# 3_4G.net
KiCad netlist of a schematic drawn in Altium Designer
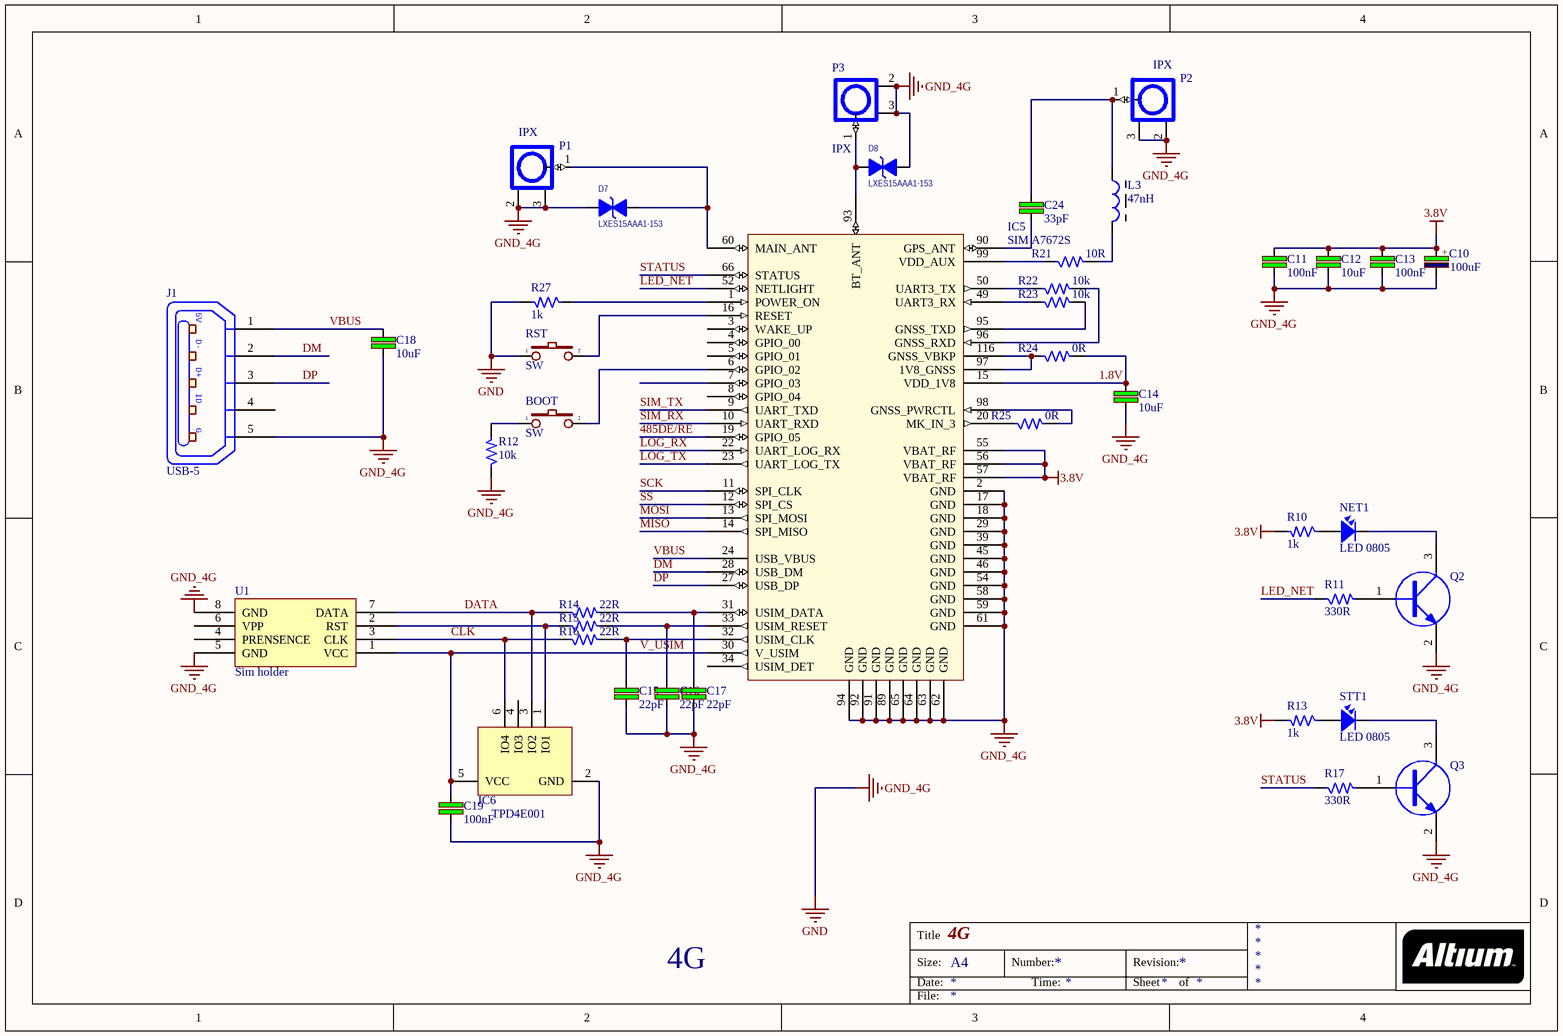
[diagram p0: 3. 4G.SchDoc]

(export (version "E")
  (design (tool "Eeschema 10.0.6"))
  (components
    (comp (ref "BOOT")
      (value "SW")
      (footprint "Anh_Trung:SW1-SMD")
      (description "Switch button 2 pin")
      (libsource (lib "Anh_Trung") (part "SW2"))
    )
    (comp (ref "C10")
      (value "100uF")
      (footprint "EEFSDE")
      (description "Cap SMD")
      (fields
        (field (name "MANUFACTURER") "Samsung Electro-Mechanics")
        (field (name "PART NUMBER") "TCME227M016R0040E")
      )
      (libsource (lib "Anh_Trung") (part "CP4"))
    )
    (comp (ref "C11")
      (value "100nF")
      (footprint "C-0805")
      (description "Cap SMD")
      (fields
        (field (name "MANUFACTURER") "Samsung Electro-Mechanics")
        (field (name "PART NUMBER") "CL21B104KBCNNWC")
      )
      (libsource (lib "") (part "C_1"))
    )
    (comp (ref "C12")
      (value "10uF")
      (footprint "C-0805")
      (description "Cap SMD")
      (fields
        (field (name "MANUFACTURER") "Samsung Electro-Mechanics")
        (field (name "PART NUMBER") "CL21A106KPFNNNG")
      )
      (libsource (lib "") (part "C_1"))
    )
    (comp (ref "C13")
      (value "100nF")
      (footprint "C-0805")
      (description "Cap SMD")
      (fields
        (field (name "MANUFACTURER") "Samsung Electro-Mechanics")
        (field (name "PART NUMBER") "CL21B104KBCNNWC")
      )
      (libsource (lib "") (part "C_1"))
    )
    (comp (ref "C14")
      (value "10uF")
      (footprint "C-0805")
      (description "Cap SMD")
      (fields
        (field (name "MANUFACTURER") "Samsung Electro-Mechanics")
        (field (name "PART NUMBER") "CL21A106KPFNNNG")
      )
      (libsource (lib "") (part "C_1"))
    )
    (comp (ref "C15")
      (value "22pF")
      (footprint "C-0805")
      (description "Cap SMD")
      (fields
        (field (name "MANUFACTURER") "Samsung Electro-Mechanics")
        (field (name "PART NUMBER") "CL21C220JBANFNC")
      )
      (libsource (lib "") (part "C_1"))
    )
    (comp (ref "C16")
      (value "22pF")
      (footprint "C-0805")
      (description "Cap SMD")
      (fields
        (field (name "MANUFACTURER") "Samsung Electro-Mechanics")
        (field (name "PART NUMBER") "CL21C220JBANFNC")
      )
      (libsource (lib "") (part "C_1"))
    )
    (comp (ref "C17")
      (value "22pF")
      (footprint "C-0805")
      (description "Cap SMD")
      (fields
        (field (name "MANUFACTURER") "Samsung Electro-Mechanics")
        (field (name "PART NUMBER") "CL21C220JBANFNC")
      )
      (libsource (lib "") (part "C_1"))
    )
    (comp (ref "C18")
      (value "10uF")
      (footprint "C-0805")
      (description "Cap SMD")
      (fields
        (field (name "MANUFACTURER") "Samsung Electro-Mechanics")
        (field (name "PART NUMBER") "CL21A106KPFNNNG")
      )
      (libsource (lib "") (part "C_2"))
    )
    (comp (ref "C19")
      (value "100nF")
      (footprint "C-0805")
      (description "Cap SMD")
      (fields
        (field (name "MANUFACTURER") "Samsung Electro-Mechanics")
        (field (name "PART NUMBER") "CL21B104KBCNNWC")
      )
      (libsource (lib "") (part "C_1"))
    )
    (comp (ref "C24")
      (value "33pF")
      (footprint "C-0805")
      (description "Cap SMD")
      (fields
        (field (name "MANUFACTURER") "Samsung Electro-Mechanics")
        (field (name "PART NUMBER") "CC0805FRNPO9BN330")
      )
      (libsource (lib "Anh_Trung") (part "C"))
    )
    (comp (ref "D7")
      (value "LXES15AAA1-153")
      (footprint "Anh_Trung:R-0402")
      (description "TVS DIODE 4VWM 1005")
      (fields (field (name "MANUFACTURER") "Murata Electronics"))
      (libsource (lib "Anh_Trung") (part "TVS"))
    )
    (comp (ref "D8")
      (value "LXES15AAA1-153")
      (footprint "Anh_Trung:R-0402")
      (description "TVS DIODE 4VWM 1005")
      (fields (field (name "MANUFACTURER") "Murata Electronics"))
      (libsource (lib "Anh_Trung") (part "TVS"))
    )
    (comp (ref "IC5")
      (value "SIM A7672S")
      (footprint "SIM A7672S")
      (description "SIM A7672S-CAT-M1")
      (libsource (lib "Anh_Trung") (part "SIM A7672S"))
    )
    (comp (ref "IC6")
      (value "TPD4E001")
      (footprint "SOT23-6 - 2")
      (fields (field (name "MANUFACTURER") "Texas Instruments") (field (name "PART NUMBER") "TPD4E001RDBVR"))
      (libsource (lib "Anh_Trung") (part "TPD4E001"))
    )
    (comp (ref "J1")
      (value "USB-5")
      (footprint "USB-M1")
      (fields (field (name "MANUFACTURER") "FCI"))
      (libsource (lib "Anh_Trung") (part "USB-5"))
    )
    (comp (ref "L3")
      (value "47nH")
      (footprint "L-0603")
      (description "FIXED IND 47NH 300MA 700MOHM SMD")
      (fields (field (name "MANUFACTURER") "Taiyo Yuden") (field (name "PART NUMBER") "HK160847NJ-T"))
      (libsource (lib "Anh_Trung") (part "Inductor Ferit"))
    )
    (comp (ref "NET1")
      (value "LED 0805")
      (footprint "LED-0805")
      (description "LED RED DIFFUSED 0805 SMD")
      (fields
        (field (name "MANUFACTURER") "OSRAM Opto Semiconductors Inc.")
        (field (name "PART NUMBER") "LS R976-NR-1")
      )
      (libsource (lib "Anh_Trung") (part "LED"))
    )
    (comp (ref "P1")
      (value "IPX")
      (footprint "IPXS")
      (description "Antenna GSM GPS")
      (fields
        (field (name "MANUFACTURER") "TE Connectivity AMP Connectors")
        (field (name "PART NUMBER") "2334884-1")
      )
      (libsource (lib "") (part "IPXSx66_1"))
    )
    (comp (ref "P2")
      (value "IPX")
      (footprint "IPXS")
      (description "Antenna GSM GPS")
      (fields
        (field (name "MANUFACTURER") "TE Connectivity AMP Connectors")
        (field (name "PART NUMBER") "2334884-1")
      )
      (libsource (lib "Anh_Trung") (part "IPXSx66"))
    )
    (comp (ref "P3")
      (value "IPX")
      (footprint "IPXS")
      (description "Antenna GSM GPS")
      (fields
        (field (name "MANUFACTURER") "TE Connectivity AMP Connectors")
        (field (name "PART NUMBER") "2334884-1")
      )
      (libsource (lib "Anh_Trung") (part "IPXSx66"))
    )
    (comp (ref "Q2")
      (value "C1815(MMBT4401)")
      (footprint "SOT23-3")
      (description "Transistor C1815, SOT23")
      (fields (field (name "MANUFACTURER") "Fairchild Semiconductor") (field (name "PART NUMBER") "MMBT4401"))
      (libsource (lib "Anh_Trung") (part "NPN"))
    )
    (comp (ref "Q3")
      (value "C1815(MMBT4401)")
      (footprint "SOT23-3")
      (description "Transistor C1815, SOT23")
      (fields (field (name "MANUFACTURER") "Fairchild Semiconductor") (field (name "PART NUMBER") "MMBT4401"))
      (libsource (lib "Anh_Trung") (part "NPN"))
    )
    (comp (ref "R10")
      (value "1k")
      (footprint "R-0805")
      (description "Resistor 1/4W")
      (fields (field (name "MANUFACTURER") "Yageo") (field (name "PART NUMBER") "RC0805FR-071KL"))
      (libsource (lib "Anh_Trung") (part "R"))
    )
    (comp (ref "R11")
      (value "330R")
      (footprint "R-0805")
      (description "Resistor 1/4W")
      (fields (field (name "MANUFACTURER") "Yageo") (field (name "PART NUMBER") "RC0805FR-07330RL"))
      (libsource (lib "Anh_Trung") (part "R"))
    )
    (comp (ref "R12")
      (value "10k")
      (footprint "R-0805")
      (description "Resistor 1/4W")
      (fields (field (name "MANUFACTURER") "Yageo") (field (name "PART NUMBER") "RC0805FR-0710KL"))
      (libsource (lib "Anh_Trung") (part "R"))
    )
    (comp (ref "R13")
      (value "1k")
      (footprint "R-0805")
      (description "Resistor 1/4W")
      (fields (field (name "MANUFACTURER") "Yageo") (field (name "PART NUMBER") "RC0805FR-071KL"))
      (libsource (lib "Anh_Trung") (part "R"))
    )
    (comp (ref "R14")
      (value "22R")
      (footprint "R-0805")
      (description "Resistor 1/4W")
      (fields (field (name "MANUFACTURER") "Yageo") (field (name "PART NUMBER") "RC0805FR-0722RL"))
      (libsource (lib "Anh_Trung") (part "R"))
    )
    (comp (ref "R15")
      (value "22R")
      (footprint "R-0805")
      (description "Resistor 1/4W")
      (fields (field (name "MANUFACTURER") "Yageo") (field (name "PART NUMBER") "RC0805FR-0722RL"))
      (libsource (lib "Anh_Trung") (part "R"))
    )
    (comp (ref "R16")
      (value "22R")
      (footprint "R-0805")
      (description "Resistor 1/4W")
      (fields (field (name "MANUFACTURER") "Yageo") (field (name "PART NUMBER") "RC0805FR-0722RL"))
      (libsource (lib "Anh_Trung") (part "R"))
    )
    (comp (ref "R17")
      (value "330R")
      (footprint "R-0805")
      (description "Resistor 1/4W")
      (fields (field (name "MANUFACTURER") "Yageo") (field (name "PART NUMBER") "RC0805FR-07330RL"))
      (libsource (lib "Anh_Trung") (part "R"))
    )
    (comp (ref "R21")
      (value "10R")
      (footprint "R-0805")
      (description "Resistor 1/4W")
      (fields (field (name "MANUFACTURER") "Yageo") (field (name "PART NUMBER") "RC0805FR-0710RL"))
      (libsource (lib "Anh_Trung") (part "R"))
    )
    (comp (ref "R22")
      (value "10k")
      (footprint "R-0805")
      (description "Resistor 1/4W")
      (fields (field (name "MANUFACTURER") "Yageo") (field (name "PART NUMBER") "RC0805FR-0710RL"))
      (libsource (lib "Anh_Trung") (part "R"))
    )
    (comp (ref "R23")
      (value "10k")
      (footprint "R-0805")
      (description "Resistor 1/4W")
      (fields (field (name "MANUFACTURER") "Yageo") (field (name "PART NUMBER") "RC0805FR-0710RL"))
      (libsource (lib "Anh_Trung") (part "R"))
    )
    (comp (ref "R24")
      (value "0R")
      (footprint "R-0805")
      (description "Resistor 1/4W")
      (fields (field (name "MANUFACTURER") "Yageo") (field (name "PART NUMBER") "RC0805FR-0710RL"))
      (libsource (lib "Anh_Trung") (part "R"))
    )
    (comp (ref "R25")
      (value "0R")
      (footprint "R-0805")
      (description "Resistor 1/4W")
      (fields (field (name "MANUFACTURER") "Yageo") (field (name "PART NUMBER") "RC0805FR-0710RL"))
      (libsource (lib "Anh_Trung") (part "R"))
    )
    (comp (ref "R27")
      (value "1k")
      (footprint "R-0805")
      (description "Resistor 1/4W")
      (fields (field (name "MANUFACTURER") "Yageo") (field (name "PART NUMBER") "RC0805FR-071KL"))
      (libsource (lib "Anh_Trung") (part "R"))
    )
    (comp (ref "RST")
      (value "SW")
      (footprint "Anh_Trung:SW1-SMD")
      (description "Switch button 2 pin")
      (libsource (lib "Anh_Trung") (part "SW2"))
    )
    (comp (ref "STT1")
      (value "LED 0805")
      (footprint "LED-0805")
      (description "LED RED DIFFUSED 0805 SMD")
      (fields
        (field (name "MANUFACTURER") "OSRAM Opto Semiconductors Inc.")
        (field (name "PART NUMBER") "LS R976-NR-1")
      )
      (libsource (lib "Anh_Trung") (part "LED"))
    )
    (comp (ref "U1")
      (value "Sim holder")
      (footprint "SIM_MicroSIM 6P Flip")
      (libsource (lib "Anh_Trung") (part "Component_1"))
    )
  )
  (nets
    (net (code "1") (name "/1.8V") (class "Default")
      (node (ref "C14") (pin "1") (pinfunction "1_1") (pintype "passive"))
      (node (ref "IC5") (pin "15") (pinfunction "VDD_1V8_15") (pintype "passive"))
      (node (ref "R24") (pin "2") (pinfunction "2_2") (pintype "passive"))
    )
    (net (code "2") (name "/485DE{slash}RE") (class "Default")
      (node (ref "IC5") (pin "19") (pinfunction "GPIO_05_19") (pintype "bidirectional"))
    )
    (net (code "3") (name "/CLK") (class "Default")
      (node (ref "IC6") (pin "6") (pinfunction "IO4_6") (pintype "passive"))
      (node (ref "R16") (pin "1") (pinfunction "1_1") (pintype "passive"))
      (node (ref "U1") (pin "3") (pinfunction "CLK_3") (pintype "passive"))
    )
    (net (code "4") (name "/DATA") (class "Default")
      (node (ref "IC6") (pin "3") (pinfunction "IO2_3") (pintype "passive"))
      (node (ref "R14") (pin "1") (pinfunction "1_1") (pintype "passive"))
      (node (ref "U1") (pin "7") (pinfunction "DATA_7") (pintype "passive"))
    )
    (net (code "5") (name "/DM") (class "Default")
      (node (ref "IC5") (pin "28") (pinfunction "USB_DM_28") (pintype "bidirectional"))
      (node (ref "J1") (pin "2") (pinfunction "P2_2") (pintype "passive"))
    )
    (net (code "6") (name "/DP") (class "Default")
      (node (ref "IC5") (pin "27") (pinfunction "USB_DP_27") (pintype "bidirectional"))
      (node (ref "J1") (pin "3") (pinfunction "P3_3") (pintype "passive"))
    )
    (net (code "7") (name "/LED_NET") (class "Default")
      (node (ref "IC5") (pin "52") (pinfunction "NETLIGHT_52") (pintype "bidirectional"))
      (node (ref "R11") (pin "1") (pinfunction "1_1") (pintype "passive"))
    )
    (net (code "8") (name "/LOG_RX") (class "Default")
      (node (ref "IC5") (pin "22") (pinfunction "UART_LOG_RX_22") (pintype "input"))
    )
    (net (code "9") (name "/LOG_TX") (class "Default")
      (node (ref "IC5") (pin "23") (pinfunction "UART_LOG_TX_23") (pintype "output"))
    )
    (net (code "10") (name "/MISO") (class "Default")
      (node (ref "IC5") (pin "14") (pinfunction "SPI_MISO_14") (pintype "output"))
    )
    (net (code "11") (name "/MOSI") (class "Default")
      (node (ref "IC5") (pin "13") (pinfunction "SPI_MOSI_13") (pintype "output"))
    )
    (net (code "12") (name "/SCK") (class "Default")
      (node (ref "IC5") (pin "11") (pinfunction "SPI_CLK_11") (pintype "bidirectional"))
    )
    (net (code "13") (name "/SIM_RX") (class "Default")
      (node (ref "IC5") (pin "10") (pinfunction "UART_RXD_10") (pintype "input"))
    )
    (net (code "14") (name "/SIM_TX") (class "Default")
      (node (ref "IC5") (pin "9") (pinfunction "UART_TXD_9") (pintype "output"))
    )
    (net (code "15") (name "/SS") (class "Default")
      (node (ref "IC5") (pin "12") (pinfunction "SPI_CS_12") (pintype "bidirectional"))
    )
    (net (code "16") (name "/STATUS") (class "Default")
      (node (ref "IC5") (pin "66") (pinfunction "STATUS_66") (pintype "bidirectional"))
      (node (ref "R17") (pin "1") (pinfunction "1_1") (pintype "passive"))
    )
    (net (code "17") (name "/VBUS") (class "Default")
      (node (ref "C18") (pin "1") (pinfunction "1_1") (pintype "passive"))
      (node (ref "IC5") (pin "24") (pinfunction "USB_VBUS_24") (pintype "passive"))
      (node (ref "J1") (pin "1") (pinfunction "P1_1") (pintype "passive"))
    )
    (net (code "18") (name "/V_USIM") (class "Default")
      (node (ref "C19") (pin "1") (pinfunction "1_1") (pintype "passive"))
      (node (ref "IC5") (pin "30") (pinfunction "V_USIM_30") (pintype "output"))
      (node (ref "IC6") (pin "5") (pinfunction "VCC_5") (pintype "passive"))
      (node (ref "U1") (pin "1") (pinfunction "VCC_1") (pintype "passive"))
    )
    (net (code "19") (name "3.8V") (class "Default")
      (node (ref "C10") (pin "1") (pinfunction "1_1") (pintype "passive"))
      (node (ref "C11") (pin "1") (pinfunction "1_1") (pintype "passive"))
      (node (ref "C12") (pin "1") (pinfunction "1_1") (pintype "passive"))
      (node (ref "C13") (pin "1") (pinfunction "1_1") (pintype "passive"))
      (node (ref "IC5") (pin "55") (pinfunction "VBAT_RF_55") (pintype "passive"))
      (node (ref "IC5") (pin "56") (pinfunction "VBAT_RF_56") (pintype "passive"))
      (node (ref "IC5") (pin "57") (pinfunction "VBAT_RF_57") (pintype "passive"))
      (node (ref "R10") (pin "2") (pinfunction "2_2") (pintype "passive"))
      (node (ref "R13") (pin "2") (pinfunction "2_2") (pintype "passive"))
    )
    (net (code "20") (name "GND") (class "Default")
      (node (ref "C10") (pin "2") (pinfunction "2_2") (pintype "passive"))
      (node (ref "C11") (pin "2") (pinfunction "2_2") (pintype "passive"))
      (node (ref "C12") (pin "2") (pinfunction "2_2") (pintype "passive"))
      (node (ref "C13") (pin "2") (pinfunction "2_2") (pintype "passive"))
      (node (ref "C14") (pin "2") (pinfunction "2_2") (pintype "passive"))
      (node (ref "C15") (pin "2") (pinfunction "2_2") (pintype "passive"))
      (node (ref "C16") (pin "2") (pinfunction "2_2") (pintype "passive"))
      (node (ref "C17") (pin "2") (pinfunction "2_2") (pintype "passive"))
      (node (ref "C18") (pin "2") (pinfunction "2_2") (pintype "passive"))
      (node (ref "C19") (pin "2") (pinfunction "2_2") (pintype "passive"))
      (node (ref "D7") (pin "2") (pinfunction "K_2") (pintype "passive"))
      (node (ref "D8") (pin "1") (pinfunction "A_1") (pintype "passive"))
      (node (ref "IC5") (pin "17") (pinfunction "GND_17") (pintype "passive"))
      (node (ref "IC5") (pin "18") (pinfunction "GND_18") (pintype "passive"))
      (node (ref "IC5") (pin "2") (pinfunction "GND_2") (pintype "passive"))
      (node (ref "IC5") (pin "29") (pinfunction "GND_29") (pintype "passive"))
      (node (ref "IC5") (pin "39") (pinfunction "GND_39") (pintype "passive"))
      (node (ref "IC5") (pin "45") (pinfunction "GND_45") (pintype "passive"))
      (node (ref "IC5") (pin "46") (pinfunction "GND_46") (pintype "passive"))
      (node (ref "IC5") (pin "54") (pinfunction "GND_54") (pintype "passive"))
      (node (ref "IC5") (pin "58") (pinfunction "GND_58") (pintype "passive"))
      (node (ref "IC5") (pin "59") (pinfunction "GND_59") (pintype "passive"))
      (node (ref "IC5") (pin "61") (pinfunction "GND_61") (pintype "passive"))
      (node (ref "IC5") (pin "62") (pinfunction "GND_62") (pintype "passive"))
      (node (ref "IC5") (pin "63") (pinfunction "GND_63") (pintype "passive"))
      (node (ref "IC5") (pin "64") (pinfunction "GND_64") (pintype "passive"))
      (node (ref "IC5") (pin "65") (pinfunction "GND_65") (pintype "passive"))
      (node (ref "IC5") (pin "89") (pinfunction "GND_89") (pintype "passive"))
      (node (ref "IC5") (pin "91") (pinfunction "GND_91") (pintype "passive"))
      (node (ref "IC5") (pin "92") (pinfunction "GND_92") (pintype "passive"))
      (node (ref "IC5") (pin "94") (pinfunction "GND_94") (pintype "passive"))
      (node (ref "IC6") (pin "2") (pinfunction "GND_2") (pintype "passive"))
      (node (ref "J1") (pin "5") (pinfunction "P5_5") (pintype "passive"))
      (node (ref "P1") (pin "2") (pintype "passive"))
      (node (ref "P1") (pin "3") (pintype "passive"))
      (node (ref "P2") (pin "2") (pintype "passive"))
      (node (ref "P2") (pin "3") (pintype "passive"))
      (node (ref "P3") (pin "2") (pintype "passive"))
      (node (ref "P3") (pin "3") (pintype "passive"))
      (node (ref "Q2") (pin "2") (pinfunction "E_2") (pintype "passive"))
      (node (ref "Q3") (pin "2") (pinfunction "E_2") (pintype "passive"))
      (node (ref "R12") (pin "1") (pinfunction "1_1") (pintype "passive"))
      (node (ref "R27") (pin "2") (pinfunction "2_2") (pintype "passive"))
      (node (ref "RST") (pin "1") (pinfunction "1_1") (pintype "passive"))
      (node (ref "U1") (pin "5") (pinfunction "GND_5") (pintype "passive"))
      (node (ref "U1") (pin "8") (pinfunction "GND_8") (pintype "passive"))
    )
    (net (code "21") (name "Net-(BOOT-Pad1)") (class "Default")
      (node (ref "BOOT") (pin "1") (pinfunction "1_1") (pintype "passive"))
      (node (ref "R12") (pin "2") (pinfunction "2_2") (pintype "passive"))
    )
    (net (code "22") (name "Net-(C24-Pad2)") (class "Default")
      (node (ref "C24") (pin "2") (pinfunction "2_2") (pintype "passive"))
      (node (ref "L3") (pin "1") (pinfunction "1_1") (pintype "passive"))
      (node (ref "P2") (pin "1") (pintype "bidirectional"))
    )
    (net (code "23") (name "Net-(D7-A)") (class "Default")
      (node (ref "D7") (pin "1") (pinfunction "A_1") (pintype "passive"))
      (node (ref "IC5") (pin "60") (pinfunction "MAIN_ANT_60") (pintype "bidirectional"))
      (node (ref "P1") (pin "1") (pintype "bidirectional"))
    )
    (net (code "24") (name "Net-(D8-K)") (class "Default")
      (node (ref "D8") (pin "2") (pinfunction "K_2") (pintype "passive"))
      (node (ref "IC5") (pin "93") (pinfunction "BT_ANT_93") (pintype "bidirectional"))
      (node (ref "P3") (pin "1") (pintype "bidirectional"))
    )
    (net (code "25") (name "Net-(IC5-1V8_GNSS)") (class "Default")
      (node (ref "IC5") (pin "116") (pinfunction "GNSS_VBKP_116") (pintype "passive"))
      (node (ref "IC5") (pin "97") (pinfunction "1V8_GNSS_97") (pintype "passive"))
      (node (ref "R24") (pin "1") (pinfunction "1_1") (pintype "passive"))
    )
    (net (code "26") (name "Net-(IC5-GNSS_PWRCTL)") (class "Default")
      (node (ref "IC5") (pin "98") (pinfunction "GNSS_PWRCTL_98") (pintype "input"))
      (node (ref "R25") (pin "2") (pinfunction "2_2") (pintype "passive"))
    )
    (net (code "27") (name "Net-(IC5-GNSS_RXD)") (class "Default")
      (node (ref "IC5") (pin "96") (pinfunction "GNSS_RXD_96") (pintype "input"))
      (node (ref "R22") (pin "2") (pinfunction "2_2") (pintype "passive"))
    )
    (net (code "28") (name "Net-(IC5-GNSS_TXD)") (class "Default")
      (node (ref "IC5") (pin "95") (pinfunction "GNSS_TXD_95") (pintype "output"))
      (node (ref "R23") (pin "2") (pinfunction "2_2") (pintype "passive"))
    )
    (net (code "29") (name "Net-(IC5-GPIO_02)") (class "Default")
      (node (ref "BOOT") (pin "2") (pinfunction "2_2") (pintype "passive"))
      (node (ref "IC5") (pin "6") (pinfunction "GPIO_02_6") (pintype "bidirectional"))
    )
    (net (code "30") (name "Net-(IC5-GPS_ANT)") (class "Default")
      (node (ref "C24") (pin "1") (pinfunction "1_1") (pintype "passive"))
      (node (ref "IC5") (pin "90") (pinfunction "GPS_ANT_90") (pintype "bidirectional"))
    )
    (net (code "31") (name "Net-(IC5-MK_IN_3)") (class "Default")
      (node (ref "IC5") (pin "20") (pinfunction "MK_IN_3_20") (pintype "output"))
      (node (ref "R25") (pin "1") (pinfunction "1_1") (pintype "passive"))
    )
    (net (code "32") (name "Net-(IC5-POWER_ON)") (class "Default")
      (node (ref "IC5") (pin "1") (pinfunction "POWER_ON_1") (pintype "input"))
      (node (ref "R27") (pin "1") (pinfunction "1_1") (pintype "passive"))
    )
    (net (code "33") (name "Net-(IC5-RESET)") (class "Default")
      (node (ref "IC5") (pin "16") (pinfunction "RESET_16") (pintype "input"))
      (node (ref "RST") (pin "2") (pinfunction "2_2") (pintype "passive"))
    )
    (net (code "34") (name "Net-(IC5-UART3_RX)") (class "Default")
      (node (ref "IC5") (pin "49") (pinfunction "UART3_RX_49") (pintype "input"))
      (node (ref "R23") (pin "1") (pinfunction "1_1") (pintype "passive"))
    )
    (net (code "35") (name "Net-(IC5-UART3_TX)") (class "Default")
      (node (ref "IC5") (pin "50") (pinfunction "UART3_TX_50") (pintype "output"))
      (node (ref "R22") (pin "1") (pinfunction "1_1") (pintype "passive"))
    )
    (net (code "36") (name "Net-(IC5-USIM_CLK)") (class "Default")
      (node (ref "C15") (pin "1") (pinfunction "1_1") (pintype "passive"))
      (node (ref "IC5") (pin "32") (pinfunction "USIM_CLK_32") (pintype "output"))
      (node (ref "R16") (pin "2") (pinfunction "2_2") (pintype "passive"))
    )
    (net (code "37") (name "Net-(IC5-USIM_DATA)") (class "Default")
      (node (ref "C17") (pin "1") (pinfunction "1_1") (pintype "passive"))
      (node (ref "IC5") (pin "31") (pinfunction "USIM_DATA_31") (pintype "bidirectional"))
      (node (ref "R14") (pin "2") (pinfunction "2_2") (pintype "passive"))
    )
    (net (code "38") (name "Net-(IC5-USIM_RESET)") (class "Default")
      (node (ref "C16") (pin "1") (pinfunction "1_1") (pintype "passive"))
      (node (ref "IC5") (pin "33") (pinfunction "USIM_RESET_33") (pintype "output"))
      (node (ref "R15") (pin "2") (pinfunction "2_2") (pintype "passive"))
    )
    (net (code "39") (name "Net-(IC5-VDD_AUX)") (class "Default")
      (node (ref "IC5") (pin "99") (pinfunction "VDD_AUX_99") (pintype "passive"))
      (node (ref "R21") (pin "1") (pinfunction "1_1") (pintype "passive"))
    )
    (net (code "40") (name "Net-(IC6-IO1)") (class "Default")
      (node (ref "IC6") (pin "1") (pinfunction "IO1_1") (pintype "passive"))
      (node (ref "R15") (pin "1") (pinfunction "1_1") (pintype "passive"))
      (node (ref "U1") (pin "2") (pinfunction "RST_2") (pintype "passive"))
    )
    (net (code "41") (name "Net-(L3-Pad2)") (class "Default")
      (node (ref "L3") (pin "2") (pinfunction "2_2") (pintype "passive"))
      (node (ref "R21") (pin "2") (pinfunction "2_2") (pintype "passive"))
    )
    (net (code "42") (name "Net-(NET1-Pad1)") (class "Default")
      (node (ref "NET1") (pin "1") (pinfunction "1_1") (pintype "passive"))
      (node (ref "R10") (pin "1") (pinfunction "1_1") (pintype "passive"))
    )
    (net (code "43") (name "Net-(Q2-B)") (class "Default")
      (node (ref "Q2") (pin "1") (pinfunction "B_1") (pintype "passive"))
      (node (ref "R11") (pin "2") (pinfunction "2_2") (pintype "passive"))
    )
    (net (code "44") (name "Net-(Q2-C)") (class "Default")
      (node (ref "NET1") (pin "2") (pinfunction "2_2") (pintype "passive"))
      (node (ref "Q2") (pin "3") (pinfunction "C_3") (pintype "passive"))
    )
    (net (code "45") (name "Net-(Q3-B)") (class "Default")
      (node (ref "Q3") (pin "1") (pinfunction "B_1") (pintype "passive"))
      (node (ref "R17") (pin "2") (pinfunction "2_2") (pintype "passive"))
    )
    (net (code "46") (name "Net-(Q3-C)") (class "Default")
      (node (ref "Q3") (pin "3") (pinfunction "C_3") (pintype "passive"))
      (node (ref "STT1") (pin "2") (pinfunction "2_2") (pintype "passive"))
    )
    (net (code "47") (name "Net-(R13-Pad1)") (class "Default")
      (node (ref "R13") (pin "1") (pinfunction "1_1") (pintype "passive"))
      (node (ref "STT1") (pin "1") (pinfunction "1_1") (pintype "passive"))
    )
    (net (code "48") (name "unconnected-(IC5-ADC1-Pad47)") (class "Default")
      (node (ref "IC5") (pin "47") (pinfunction "ADC1_47") (pintype "passive"))
    )
    (net (code "49") (name "unconnected-(IC5-ADC2-Pad46)") (class "Default")
      (node (ref "IC5") (pin "46") (pinfunction "ADC2_46") (pintype "passive"))
    )
    (net (code "50") (name "unconnected-(IC5-EAR1N-Pad25)") (class "Default")
      (node (ref "IC5") (pin "25") (pinfunction "EAR1N_25") (pintype "passive"))
    )
    (net (code "51") (name "unconnected-(IC5-EAR1P-Pad26)") (class "Default")
      (node (ref "IC5") (pin "26") (pinfunction "EAR1P_26") (pintype "passive"))
    )
    (net (code "52") (name "unconnected-(IC5-GPIO1-Pad51)") (class "Default")
      (node (ref "IC5") (pin "51") (pinfunction "GPIO1_51") (pintype "passive"))
    )
    (net (code "53") (name "unconnected-(IC5-GPIO4-Pad54)") (class "Default")
      (node (ref "IC5") (pin "54") (pinfunction "GPIO4_54") (pintype "passive"))
    )
    (net (code "54") (name "unconnected-(IC5-GPIO40-Pad49)") (class "Default")
      (node (ref "IC5") (pin "49") (pinfunction "GPIO40_49") (pintype "passive"))
    )
    (net (code "55") (name "unconnected-(IC5-GPIO41-Pad52)") (class "Default")
      (node (ref "IC5") (pin "52") (pinfunction "GPIO41_52") (pintype "passive"))
    )
    (net (code "56") (name "unconnected-(IC5-GPIO42-Pad53)") (class "Default")
      (node (ref "IC5") (pin "53") (pinfunction "GPIO42_53") (pintype "passive"))
    )
    (net (code "57") (name "unconnected-(IC5-GPIO43-Pad50)") (class "Default")
      (node (ref "IC5") (pin "50") (pinfunction "GPIO43_50") (pintype "passive"))
    )
    (net (code "58") (name "unconnected-(IC5-GPIO44-Pad48)") (class "Default")
      (node (ref "IC5") (pin "48") (pinfunction "GPIO44_48") (pintype "passive"))
    )
    (net (code "59") (name "unconnected-(IC5-GPIO_00-Pad4)") (class "Default")
      (node (ref "IC5") (pin "4") (pinfunction "GPIO_00_4") (pintype "bidirectional"))
    )
    (net (code "60") (name "unconnected-(IC5-GPIO_01-Pad5)") (class "Default")
      (node (ref "IC5") (pin "5") (pinfunction "GPIO_01_5") (pintype "bidirectional"))
    )
    (net (code "61") (name "unconnected-(IC5-GPIO_03-Pad7)") (class "Default")
      (node (ref "IC5") (pin "7") (pinfunction "GPIO_03_7") (pintype "bidirectional"))
    )
    (net (code "62") (name "unconnected-(IC5-GPIO_04-Pad8)") (class "Default")
      (node (ref "IC5") (pin "8") (pinfunction "GPIO_04_8") (pintype "bidirectional"))
    )
    (net (code "63") (name "unconnected-(IC5-KEYPAD_0-Pad29)") (class "Default")
      (node (ref "IC5") (pin "29") (pinfunction "KEYPAD_0_29") (pintype "passive"))
    )
    (net (code "64") (name "unconnected-(IC5-KEYPAD_1-Pad33)") (class "Default")
      (node (ref "IC5") (pin "33") (pinfunction "KEYPAD_1_33") (pintype "passive"))
    )
    (net (code "65") (name "unconnected-(IC5-KEYPAD_2-Pad30)") (class "Default")
      (node (ref "IC5") (pin "30") (pinfunction "KEYPAD_2_30") (pintype "passive"))
    )
    (net (code "66") (name "unconnected-(IC5-KEYPAD_3-Pad35)") (class "Default")
      (node (ref "IC5") (pin "35") (pinfunction "KEYPAD_3_35") (pintype "passive"))
    )
    (net (code "67") (name "unconnected-(IC5-KEYPAD_4-Pad34)") (class "Default")
      (node (ref "IC5") (pin "34") (pinfunction "KEYPAD_4_34") (pintype "passive"))
    )
    (net (code "68") (name "unconnected-(IC5-KEYSENSE_N0-Pad28)") (class "Default")
      (node (ref "IC5") (pin "28") (pinfunction "KEYSENSE_N0_28") (pintype "passive"))
    )
    (net (code "69") (name "unconnected-(IC5-KEYSENSE_N1-Pad27)") (class "Default")
      (node (ref "IC5") (pin "27") (pinfunction "KEYSENSE_N1_27") (pintype "passive"))
    )
    (net (code "70") (name "unconnected-(IC5-KEYSENSE_N2-Pad31)") (class "Default")
      (node (ref "IC5") (pin "31") (pinfunction "KEYSENSE_N2_31") (pintype "passive"))
    )
    (net (code "71") (name "unconnected-(IC5-KEYSENSE_N3-Pad32)") (class "Default")
      (node (ref "IC5") (pin "32") (pinfunction "KEYSENSE_N3_32") (pintype "passive"))
    )
    (net (code "72") (name "unconnected-(IC5-KEYSENSE_N4-Pad36)") (class "Default")
      (node (ref "IC5") (pin "36") (pinfunction "KEYSENSE_N4_36") (pintype "passive"))
    )
    (net (code "73") (name "unconnected-(IC5-MIC1N-Pad24)") (class "Default")
      (node (ref "IC5") (pin "24") (pinfunction "MIC1N_24") (pintype "passive"))
    )
    (net (code "74") (name "unconnected-(IC5-MIC1P-Pad23)") (class "Default")
      (node (ref "IC5") (pin "23") (pinfunction "MIC1P_23") (pintype "passive"))
    )
    (net (code "75") (name "unconnected-(IC5-PCM_CLK-Pad76)") (class "Default")
      (node (ref "IC5") (pin "76") (pinfunction "PCM_CLK_76") (pintype "passive"))
    )
    (net (code "76") (name "unconnected-(IC5-PCM_DIN-Pad74)") (class "Default")
      (node (ref "IC5") (pin "74") (pinfunction "PCM_DIN_74") (pintype "passive"))
    )
    (net (code "77") (name "unconnected-(IC5-PCM_DOUT-Pad73)") (class "Default")
      (node (ref "IC5") (pin "73") (pinfunction "PCM_DOUT_73") (pintype "passive"))
    )
    (net (code "78") (name "unconnected-(IC5-PCM_SYNC-Pad75)") (class "Default")
      (node (ref "IC5") (pin "75") (pinfunction "PCM_SYNC_75") (pintype "passive"))
    )
    (net (code "79") (name "unconnected-(IC5-RESERVED-Pad15)") (class "Default")
      (node (ref "IC5") (pin "15") (pinfunction "RESERVED_15") (pintype "passive"))
    )
    (net (code "80") (name "unconnected-(IC5-RESERVED-Pad16)") (class "Default")
      (node (ref "IC5") (pin "16") (pinfunction "RESERVED_16") (pintype "passive"))
    )
    (net (code "81") (name "unconnected-(IC5-SPK_M-Pad21)") (class "Default")
      (node (ref "IC5") (pin "21") (pinfunction "SPK_M_21") (pintype "passive"))
    )
    (net (code "82") (name "unconnected-(IC5-SPK_P-Pad22)") (class "Default")
      (node (ref "IC5") (pin "22") (pinfunction "SPK_P_22") (pintype "passive"))
    )
    (net (code "83") (name "unconnected-(IC5-USIM_DET-Pad34)") (class "Default")
      (node (ref "IC5") (pin "34") (pinfunction "USIM_DET_34") (pintype "output"))
    )
    (net (code "84") (name "unconnected-(IC5-WAKE_UP-Pad3)") (class "Default")
      (node (ref "IC5") (pin "3") (pinfunction "WAKE_UP_3") (pintype "bidirectional"))
    )
    (net (code "85") (name "unconnected-(IC6-IO3-Pad4)") (class "Default")
      (node (ref "IC6") (pin "4") (pinfunction "IO3_4") (pintype "passive"))
    )
    (net (code "86") (name "unconnected-(J1-P4-Pad4)") (class "Default")
      (node (ref "J1") (pin "4") (pinfunction "P4_4") (pintype "passive"))
    )
    (net (code "87") (name "unconnected-(U1-PRENSENCE-Pad4)") (class "Default")
      (node (ref "U1") (pin "4") (pinfunction "PRENSENCE_4") (pintype "passive"))
    )
    (net (code "88") (name "unconnected-(U1-VPP-Pad6)") (class "Default")
      (node (ref "U1") (pin "6") (pinfunction "VPP_6") (pintype "passive"))
    )
  )
)
